# Shett_3.net
KiCad netlist of a schematic drawn in Altium Designer
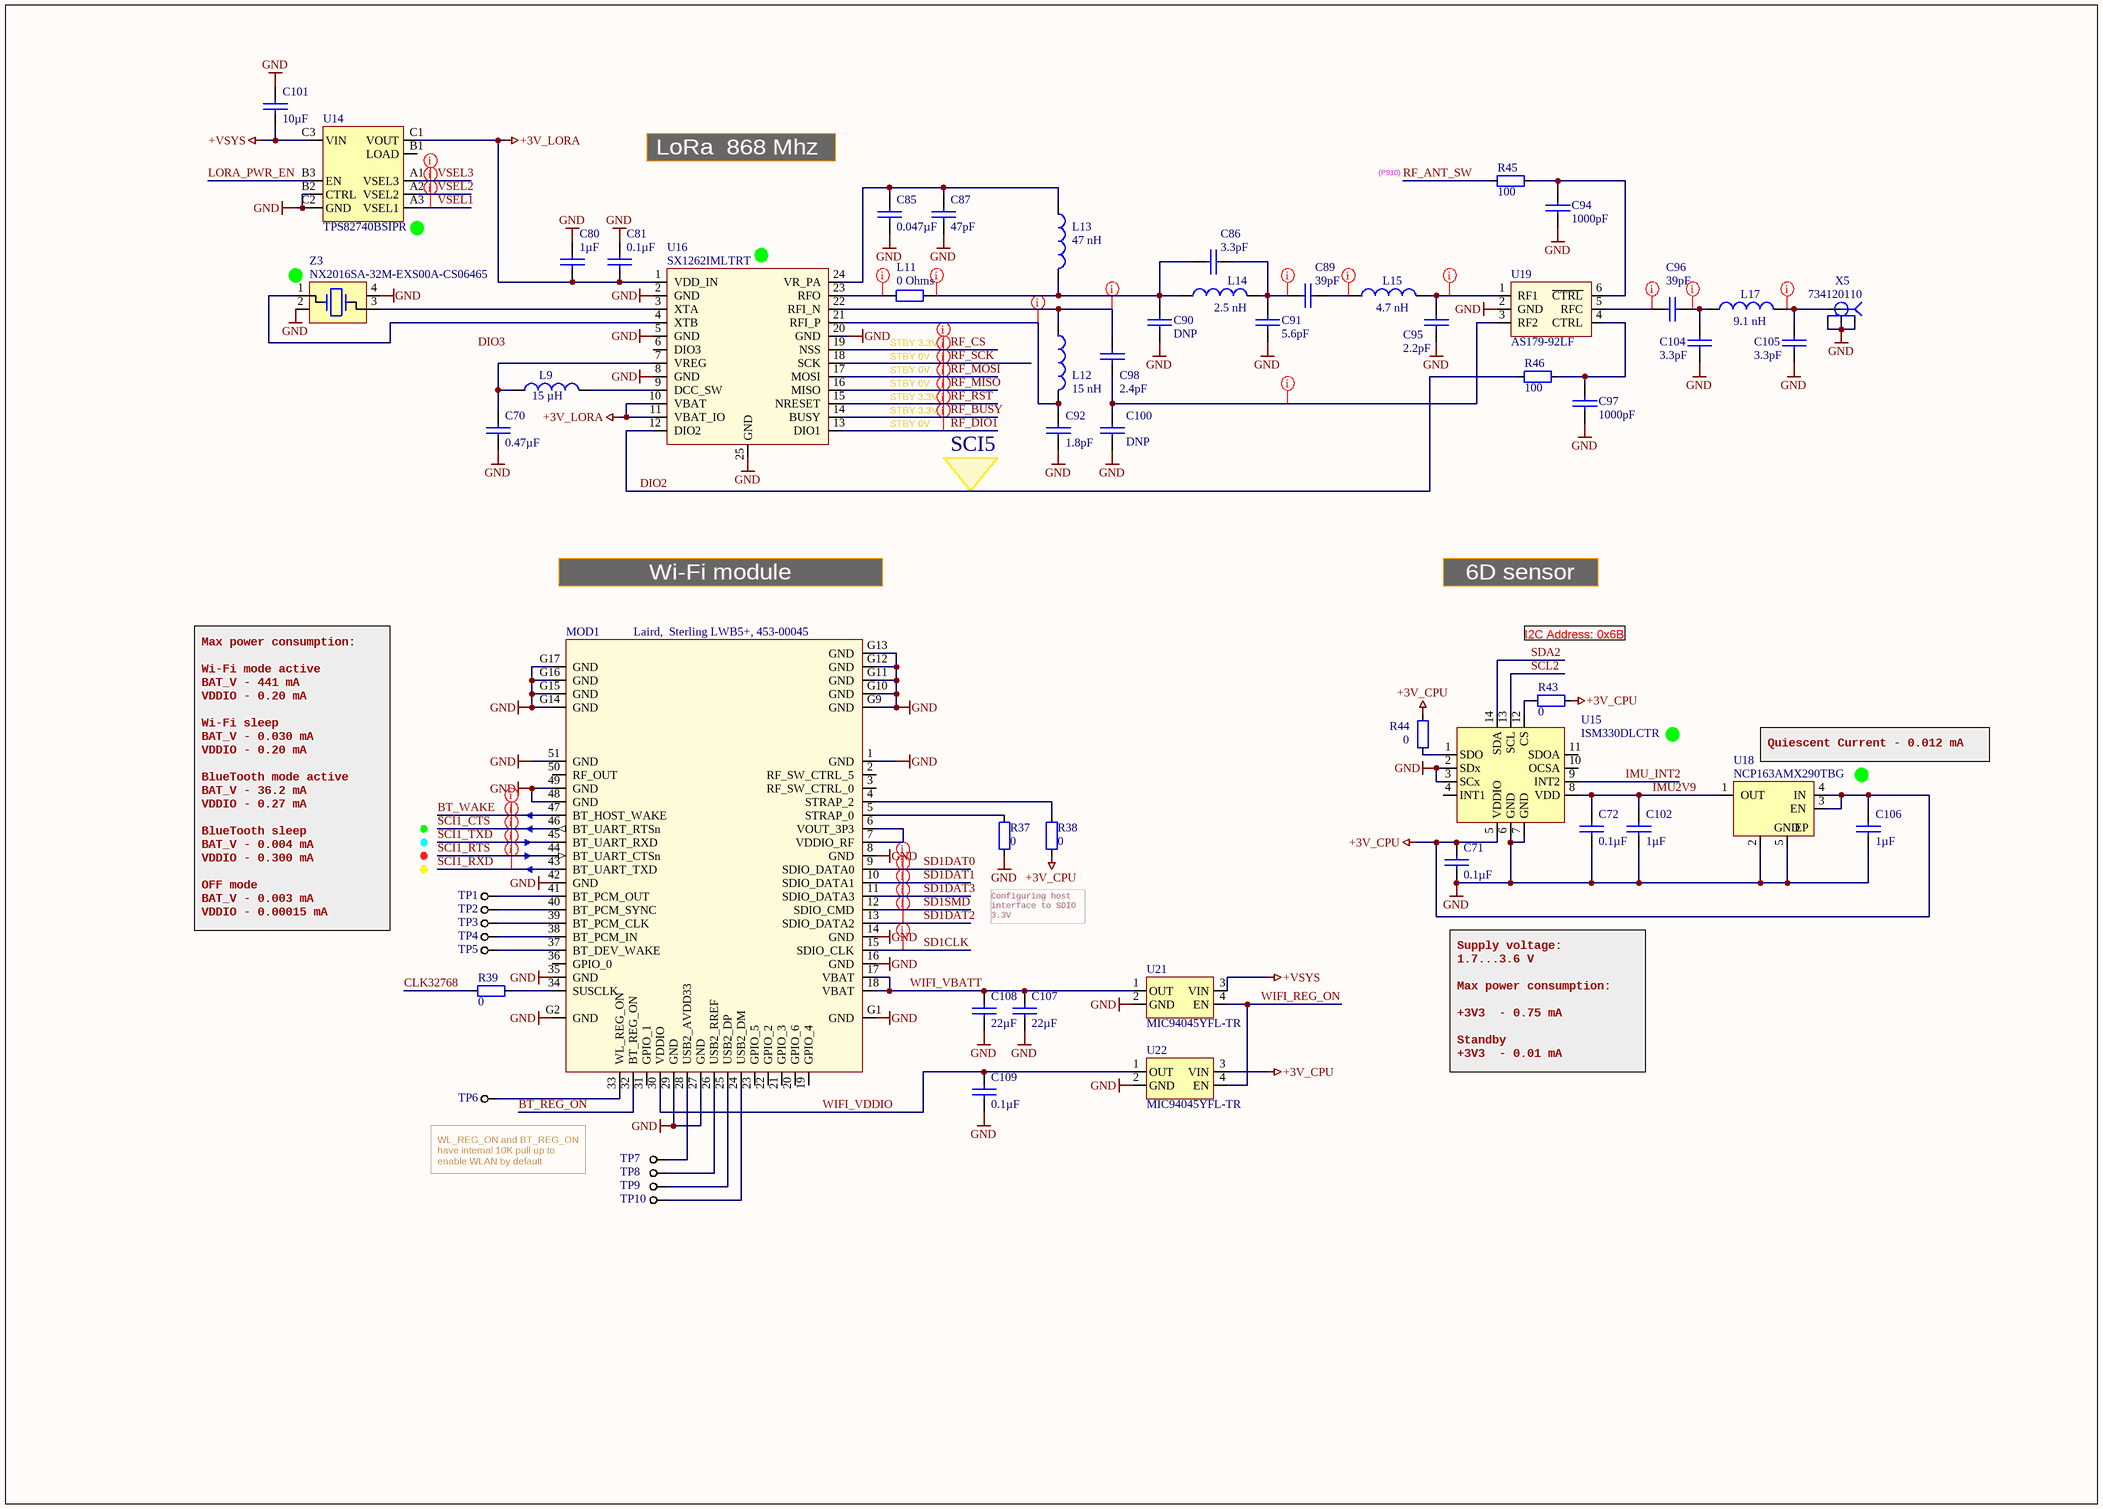
[diagram p0: Shett_3.SchDoc]

(export (version "E")
  (design (tool "Eeschema 10.0.6"))
  (components
    (comp (ref "C70")
      (value "0.47µF")
      (footprint "0402 CAP")
      (description "0.47µF, ±20%, 25V, X5R, 0402 (1005 Metric), -55°C ~ 85°C, -, Automotive")
      (fields
        (field (name "PART NUMBER") "GRT155R61E474ME01D")
        (field (name "MANUFACTURER") "Murata Electronics North America")
      )
      (libsource (lib "ea_PassivComps") (part "Capacitor"))
    )
    (comp (ref "C71")
      (value "0.1µF")
      (footprint "0402 CAP")
      (description "0.1µF, ±10%, 50V, X7R, 0402 (1005 Metric), -55°C ~ 125°C, -, General Purpose")
      (fields
        (field (name "PART NUMBER") "0402B104K500CT")
        (field (name "MANUFACTURER") "Walsin Technology Corporation")
      )
      (libsource (lib "ea_PassivComps") (part "Capacitor"))
    )
    (comp (ref "C72")
      (value "0.1µF")
      (footprint "0402 CAP")
      (description "0.1µF, ±10%, 50V, X7R, 0402 (1005 Metric), -55°C ~ 125°C, -, General Purpose")
      (fields
        (field (name "PART NUMBER") "0402B104K500CT")
        (field (name "MANUFACTURER") "Walsin Technology Corporation")
      )
      (libsource (lib "ea_PassivComps") (part "Capacitor"))
    )
    (comp (ref "C80")
      (value "1µF")
      (footprint "0402 CAP")
      (description "1µF, ±20%, 25V, X5R, 0402 (1005 Metric), -55°C ~ 85°C, -, General Purpose")
      (fields (field (name "PART NUMBER") "TMK105BJ105MV-F") (field (name "MANUFACTURER") "Taiyo Yuden"))
      (libsource (lib "ea_PassivComps") (part "Capacitor"))
    )
    (comp (ref "C81")
      (value "0.1µF")
      (footprint "0402 CAP")
      (description "0.1µF, ±10%, 50V, X7R, 0402 (1005 Metric), -55°C ~ 125°C, -, General Purpose")
      (fields
        (field (name "PART NUMBER") "0402B104K500CT")
        (field (name "MANUFACTURER") "Walsin Technology Corporation")
      )
      (libsource (lib "ea_PassivComps") (part "Capacitor"))
    )
    (comp (ref "C85")
      (value "0.047µF")
      (footprint "0402 CAP")
      (description "0.047µF, ±10%, 25V, X7R, 0402 (1005 Metric), -55°C ~ 125°C, -, General Purpose")
      (fields (field (name "PART NUMBER") "CC0402KRX7R8BB473") (field (name "MANUFACTURER") "Yageo"))
      (libsource (lib "ea_PassivComps") (part "Capacitor"))
    )
    (comp (ref "C86")
      (value "3.3pF")
      (footprint "0402 CAP")
      (description "3.3pF, ±0.1pF, 50V, C0G, NP0, 0402 (1005 Metric), -55°C ~ 125°C, -, RF, Microwave, High Frequency")
      (fields
        (field (name "PART NUMBER") "885392005011")
        (field (name "MANUFACTURER") "Wurth Electronics Inc.")
      )
      (libsource (lib "ea_PassivComps") (part "Capacitor"))
    )
    (comp (ref "C87")
      (value "47pF")
      (footprint "0402 CAP")
      (fields
        (field (name "PART NUMBER") "GJM1555C1H470FB01D")
        (field (name "MANUFACTURER") "Murata Electronics North America")
        (field (name "PARTNUM") "490-16376-1-ND")
      )
      (libsource (lib "ea_PassivComps") (part "Capacitor"))
    )
    (comp (ref "C89")
      (value "39pF")
      (footprint "0402 CAP")
      (fields
        (field (name "PART NUMBER") "GJM1555C1H390JB01D")
        (field (name "MANUFACTURER") "Murata Electronics North America")
        (field (name "PARTNUM") "490-17673-1-ND")
      )
      (libsource (lib "ea_PassivComps") (part "Capacitor"))
    )
    (comp (ref "C90")
      (value "DNP")
      (footprint "0402 CAP")
      (fields (field (name "Comment") "Capacitor_0402"))
      (libsource (lib "ea_Capacitors") (part "Capacitor_0402"))
    )
    (comp (ref "C91")
      (value "5.6pF")
      (footprint "0402 CAP")
      (fields
        (field (name "PART NUMBER") "GJM1555C1H5R6BB01D")
        (field (name "MANUFACTURER") "Murata Electronics North America")
        (field (name "PARTNUM") "490-11225-1-ND")
      )
      (libsource (lib "ea_PassivComps") (part "Capacitor"))
    )
    (comp (ref "C92")
      (value "1.8pF")
      (footprint "0402 CAP")
      (fields
        (field (name "PART NUMBER") "GJM1555C1H1R8BB01D")
        (field (name "MANUFACTURER") "Murata Electronics North America")
        (field (name "PARTNUM") "490-8089-1-ND")
      )
      (libsource (lib "ea_PassivComps") (part "Capacitor"))
    )
    (comp (ref "C94")
      (value "1000pF")
      (footprint "0402 CAP")
      (description "1000pF, ±5%, 50V, CH, 0402 (1005 Metric), -25°C ~ 85°C, Low ESL, General Purpose")
      (fields
        (field (name "PART NUMBER") "C1005CH1H102J050BA")
        (field (name "MANUFACTURER") "TDK Corporation")
      )
      (libsource (lib "ea_PassivComps") (part "Capacitor"))
    )
    (comp (ref "C95")
      (value "2.2pF")
      (footprint "0402 CAP")
      (fields
        (field (name "PART NUMBER") "CBR04C229B5GAC")
        (field (name "MANUFACTURER") "KEMET")
        (field (name "PARTNUM") "399-17527-1-ND")
      )
      (libsource (lib "ea_PassivComps") (part "Capacitor"))
    )
    (comp (ref "C96")
      (value "39pF")
      (footprint "0402 CAP")
      (fields
        (field (name "PART NUMBER") "GJM1555C1H390JB01D")
        (field (name "MANUFACTURER") "Murata Electronics North America")
        (field (name "PARTNUM") "490-17673-1-ND")
      )
      (libsource (lib "ea_PassivComps") (part "Capacitor"))
    )
    (comp (ref "C97")
      (value "1000pF")
      (footprint "0402 CAP")
      (description "1000pF, ±5%, 50V, CH, 0402 (1005 Metric), -25°C ~ 85°C, Low ESL, General Purpose")
      (fields
        (field (name "PART NUMBER") "C1005CH1H102J050BA")
        (field (name "MANUFACTURER") "TDK Corporation")
      )
      (libsource (lib "ea_PassivComps") (part "Capacitor"))
    )
    (comp (ref "C98")
      (value "2.4pF")
      (footprint "0402 CAP")
      (fields
        (field (name "PART NUMBER") "GJM1555C1H2R4BB01D")
        (field (name "MANUFACTURER") "Murata Electronics North America")
        (field (name "PARTNUM") "490-8093-1-ND")
      )
      (libsource (lib "ea_PassivComps") (part "Capacitor"))
    )
    (comp (ref "C100")
      (value "DNP")
      (footprint "0402 CAP")
      (fields (field (name "Comment") "Capacitor_0402"))
      (libsource (lib "ea_Capacitors") (part "Capacitor_0402"))
    )
    (comp (ref "C101")
      (value "10µF")
      (footprint "0603 CAP")
      (description "10µF, ±10%, 16V, X5R, 0603 (1608 Metric), -55°C ~ 85°C, -, Automotive")
      (fields
        (field (name "PART NUMBER") "GRT188R61C106KE13D")
        (field (name "MANUFACTURER") "Murata Electronics North America")
      )
      (libsource (lib "ea_PassivComps") (part "Capacitor"))
    )
    (comp (ref "C102")
      (value "1µF")
      (footprint "0402 CAP")
      (description "1µF, ±20%, 25V, X5R, 0402 (1005 Metric), -55°C ~ 85°C, -, General Purpose")
      (fields (field (name "PART NUMBER") "TMK105BJ105MV-F") (field (name "MANUFACTURER") "Taiyo Yuden"))
      (libsource (lib "ea_PassivComps") (part "Capacitor"))
    )
    (comp (ref "C104")
      (value "3.3pF")
      (footprint "0402 CAP")
      (description "3.3pF, ±0.1pF, 50V, C0G, NP0, 0402 (1005 Metric), -55°C ~ 125°C, -, RF, Microwave, High Frequency")
      (fields
        (field (name "PART NUMBER") "885392005011")
        (field (name "MANUFACTURER") "Wurth Electronics Inc.")
      )
      (libsource (lib "ea_PassivComps") (part "Capacitor"))
    )
    (comp (ref "C105")
      (value "3.3pF")
      (footprint "0402 CAP")
      (description "3.3pF, ±0.1pF, 50V, C0G, NP0, 0402 (1005 Metric), -55°C ~ 125°C, -, RF, Microwave, High Frequency")
      (fields
        (field (name "PART NUMBER") "885392005011")
        (field (name "MANUFACTURER") "Wurth Electronics Inc.")
      )
      (libsource (lib "ea_PassivComps") (part "Capacitor"))
    )
    (comp (ref "C106")
      (value "1µF")
      (footprint "0402 CAP")
      (description "1µF, ±20%, 25V, X5R, 0402 (1005 Metric), -55°C ~ 85°C, -, General Purpose")
      (fields (field (name "PART NUMBER") "TMK105BJ105MV-F") (field (name "MANUFACTURER") "Taiyo Yuden"))
      (libsource (lib "ea_PassivComps") (part "Capacitor"))
    )
    (comp (ref "C107")
      (value "22µF")
      (footprint "0603 CAP")
      (description "22µF, ±20%, 10V, X5R, 0603 (1608 Metric), -55°C ~ 85°C, -, SMPS Filtering")
      (fields (field (name "PART NUMBER") "LMK107BBJ226MA-T") (field (name "MANUFACTURER") "Taiyo Yuden"))
      (libsource (lib "ea_PassivComps") (part "Capacitor"))
    )
    (comp (ref "C108")
      (value "22µF")
      (footprint "0603 CAP")
      (description "22µF, ±20%, 10V, X5R, 0603 (1608 Metric), -55°C ~ 85°C, -, SMPS Filtering")
      (fields (field (name "PART NUMBER") "LMK107BBJ226MA-T") (field (name "MANUFACTURER") "Taiyo Yuden"))
      (libsource (lib "ea_PassivComps") (part "Capacitor"))
    )
    (comp (ref "C109")
      (value "0.1µF")
      (footprint "0402 CAP")
      (description "0.1µF, ±10%, 50V, X7R, 0402 (1005 Metric), -55°C ~ 125°C, -, General Purpose")
      (fields
        (field (name "PART NUMBER") "0402B104K500CT")
        (field (name "MANUFACTURER") "Walsin Technology Corporation")
      )
      (libsource (lib "ea_PassivComps") (part "Capacitor"))
    )
    (comp (ref "L9")
      (value "15 µH")
      (footprint "2012[0805]")
      (description "15 µH Shielded Multilayer Inductor 250 mA, 1.235Ohm, 24MHz Max 0805 (2012 Metric)")
      (fields
        (field (name "MANUFACTURER") "Murata Electronics")
        (field (name "PARTNUM") "490-LQM21DH150M70LCT-ND")
      )
      (libsource (lib "ea_RF_inductors") (part "LQM21DH150M70L"))
    )
    (comp (ref "L11")
      (value "0 Ohms")
      (footprint "INDC1005-0402")
      (description "0 Ohms Jumper 0.063W, 1/16W Chip Resistor 0402 (1005 Metric) Automotive AEC-Q200 Thick Film")
      (fields (field (name "MANUFACTURER") "Vishay Dale") (field (name "PARTNUM") "541-0.0JCT-ND"))
      (libsource (lib "ea_RF_inductors") (part "CRCW04020000Z0ED"))
    )
    (comp (ref "L12")
      (value "15 nH")
      (footprint "INDC1005-0402")
      (description "15nH Unshielded Wirewound Inductor 460mA 160 mOhm Max 0402 (1006 Metric)")
      (fields (field (name "MANUFACTURER") "Murata") (field (name "TOLERANCE") "±3%"))
      (libsource (lib "ea_RF_inductors") (part "LQW15AN15NH00D"))
    )
    (comp (ref "L13")
      (value "47 nH")
      (footprint "INDC1005-0402")
      (description "47nH Unshielded Wirewound Inductor 210mA 1.08 Ohm Max 0402 (1005 Metric)")
      (fields (field (name "MANUFACTURER") "Murata") (field (name "TOLERANCE") "±5%"))
      (libsource (lib "ea_RF_inductors") (part "LQW15AN47NJ00D"))
    )
    (comp (ref "L14")
      (value "2.5 nH")
      (footprint "INDC1005-0402")
      (description "2.5nH Unshielded Wirewound Inductor 850mA 50 mOhm Max 0402 (1006 Metric)")
      (fields (field (name "MANUFACTURER") "Murata") (field (name "TOLERANCE") "±0.2nH"))
      (libsource (lib "ea_RF_inductors") (part "LQW15AN2N5C00D"))
    )
    (comp (ref "L15")
      (value "4.7 nH")
      (footprint "INDC1005-0402")
      (description "4.7nH Unshielded Wirewound Inductor 750mA 70 mOhm Max 0402 (1006 Metric)")
      (fields
        (field (name "MANUFACTURER") "Murata Electronics North America")
        (field (name "TOLERANCE") "±0.2nH")
      )
      (libsource (lib "ea_RF_inductors") (part "LQW15AN4N7C00D"))
    )
    (comp (ref "L17")
      (value "9.1 nH")
      (footprint "INDC1005-0402")
      (description "9.1nH Unshielded Wirewound Inductor 540mA 140 mOhm Max 0402 (1006 Metric)")
      (fields
        (field (name "MANUFACTURER") "Murata Electronics North America")
        (field (name "TOLERANCE") "±3%")
      )
      (libsource (lib "ea_RF_inductors") (part "LQW15AN9N1H00D"))
    )
    (comp (ref "MOD1")
      (value "Laird,  Sterling LWB5+, 453-00045")
      (footprint "LWB5+ 453-00045C ver S7V30")
      (description "Module, Sterling LWB5+")
      (fields (field (name "MANUFACTURER") "Laird"))
      (libsource (lib "ea_WiFi_modules") (part "CMP-MOD-453-00012-1.4_ver_S7V30"))
    )
    (comp (ref "R37")
      (value "0")
      (footprint "0402")
      (description "0 Ohms Jumper 0.063W, 1/16W Chip Resistor 0402 (1005 Metric) Thick Film")
      (fields (field (name "MANUFACTURER") "Walsin Technology Corporation") (field (name "VOLTAGE") "50 V"))
      (libsource (lib "") (part "WR04X000 PTL_1"))
    )
    (comp (ref "R38")
      (value "0")
      (footprint "0402")
      (description "0 Ohms Jumper 0.063W, 1/16W Chip Resistor 0402 (1005 Metric) Thick Film")
      (fields (field (name "MANUFACTURER") "Walsin Technology Corporation") (field (name "VOLTAGE") "50 V"))
      (libsource (lib "") (part "WR04X000 PTL_1"))
    )
    (comp (ref "R39")
      (value "0")
      (footprint "0402")
      (description "0 Ohms Jumper 0.063W, 1/16W Chip Resistor 0402 (1005 Metric) Thick Film")
      (fields (field (name "MANUFACTURER") "Walsin Technology Corporation") (field (name "VOLTAGE") "50 V"))
      (libsource (lib "ea_Resistors_0402") (part "WR04X000 PTL"))
    )
    (comp (ref "R43")
      (value "0")
      (footprint "0402")
      (description "0 Ohms Jumper 0.063W, 1/16W Chip Resistor 0402 (1005 Metric) Thick Film")
      (fields (field (name "MANUFACTURER") "Walsin Technology Corporation") (field (name "VOLTAGE") "50 V"))
      (libsource (lib "ea_Resistors_0402") (part "WR04X000 PTL"))
    )
    (comp (ref "R44")
      (value "0")
      (footprint "0402")
      (description "0 Ohms Jumper 0.063W, 1/16W Chip Resistor 0402 (1005 Metric) Thick Film")
      (fields (field (name "MANUFACTURER") "Walsin Technology Corporation") (field (name "VOLTAGE") "50 V"))
      (libsource (lib "") (part "WR04X000 PTL_1"))
    )
    (comp (ref "R45")
      (value "100")
      (footprint "0402")
      (fields
        (field (name "MANUFACTURER") "Stackpole Electronics Inc")
        (field (name "TOLERANCE") "±1%")
        (field (name "VOLTAGE") "75V")
      )
      (libsource (lib "ea_PassivComps") (part "Resistor"))
    )
    (comp (ref "R46")
      (value "100")
      (footprint "0402")
      (fields
        (field (name "MANUFACTURER") "Stackpole Electronics Inc")
        (field (name "TOLERANCE") "±1%")
        (field (name "VOLTAGE") "75V")
      )
      (libsource (lib "ea_PassivComps") (part "Resistor"))
    )
    (comp (ref "TP1")
      (value "Test_point 0.5 мм")
      (footprint "Test point 0.5 мм")
      (libsource (lib "ea_Contacts") (part "Test_point 0.5 мм"))
    )
    (comp (ref "TP2")
      (value "Test_point 0.5 мм")
      (footprint "Test point 0.5 мм")
      (libsource (lib "ea_Contacts") (part "Test_point 0.5 мм"))
    )
    (comp (ref "TP3")
      (value "Test_point 0.5 мм")
      (footprint "Test point 0.5 мм")
      (libsource (lib "ea_Contacts") (part "Test_point 0.5 мм"))
    )
    (comp (ref "TP4")
      (value "Test_point 0.5 мм")
      (footprint "Test point 0.5 мм")
      (libsource (lib "ea_Contacts") (part "Test_point 0.5 мм"))
    )
    (comp (ref "TP5")
      (value "Test_point 0.5 мм")
      (footprint "Test point 0.5 мм")
      (libsource (lib "ea_Contacts") (part "Test_point 0.5 мм"))
    )
    (comp (ref "TP6")
      (value "Test_point 0.5 мм")
      (footprint "Test point 0.5 мм")
      (libsource (lib "ea_Contacts") (part "Test_point 0.5 мм"))
    )
    (comp (ref "TP7")
      (value "Test_point 0.5 мм")
      (footprint "Test point 0.5 мм")
      (libsource (lib "ea_Contacts") (part "Test_point 0.5 мм"))
    )
    (comp (ref "TP8")
      (value "Test_point 0.5 мм")
      (footprint "Test point 0.5 мм")
      (libsource (lib "ea_Contacts") (part "Test_point 0.5 мм"))
    )
    (comp (ref "TP9")
      (value "Test_point 0.5 мм")
      (footprint "Test point 0.5 мм")
      (libsource (lib "ea_Contacts") (part "Test_point 0.5 мм"))
    )
    (comp (ref "TP10")
      (value "Test_point 0.5 мм")
      (footprint "Test point 0.5 мм")
      (libsource (lib "ea_Contacts") (part "Test_point 0.5 мм"))
    )
    (comp (ref "U14")
      (value "TPS82740BSIPR")
      (footprint "MicroSiP")
      (fields (field (name "MANUFACTURER") "Texas Instruments") (field (name "PARTNUM") "296-46481-1-ND"))
      (libsource (lib "ea_IC_Power_Reg_Ref_Sw") (part "TPS82740BSIPR"))
    )
    (comp (ref "U15")
      (value "ISM330DLCTR")
      (footprint "LGA-14 BOSCH")
      (description "Accelerometer, Gyroscope, Temperature, 3 Axis Sensor I²C, SPI , -40°C ~ 85°C, 14-LGA (2.5x3)")
      (fields (field (name "MANUFACTURER") "STMicroelectronics") (field (name "PARTNUM") "497-17583-1-ND"))
      (libsource (lib "ea_IC_sensors") (part "ISM330DLCTR"))
    )
    (comp (ref "U16")
      (value "SX1262IMLTRT")
      (footprint "VQFN24")
      (description "IC RF TxRx Only General ISM < 1GHz LoRaWAN 150MHz ~ 960MHz 24-VFQFN Exposed Pad")
      (fields (field (name "MANUFACTURER") "Semtech Corporation"))
      (libsource (lib "ea_IC_RF") (part "SX1262IMLTRT"))
    )
    (comp (ref "U18")
      (value "NCP163AMX290TBG")
      (footprint "4-XDFN")
      (description "LDO 2.9V, 250 mA, Vin < 5.5V, Iq < 20uA, PSSR 91dB ~ 60dB, -40..+125 C,  4-XDFN (1x1)")
      (fields
        (field (name "MANUFACTURER") "ON Semiconductor")
        (field (name "PARTNUM") "NCP163AMX290TBGOSCT-ND")
      )
      (libsource (lib "ea_IC_Linear_reg_LDO") (part "NCP163AMX290TBG"))
    )
    (comp (ref "U19")
      (value "AS179-92LF")
      (footprint "SC70-6")
      (description "RF Switch IC 802.11b, g, Bluetooth, WLAN SPDT 3 GHz 50Ohm SC-70-6, -40°C ~ 85°C")
      (fields
        (field (name "MANUFACTURER") "Skyworks Solutions Inc.")
        (field (name "PARTNUM") "863-1003-1-ND")
        (field (name "PARTNAME") "AS179-92LF")
      )
      (libsource (lib "ea_IC_RF") (part "AS179-92LF"))
    )
    (comp (ref "U21")
      (value "MIC94045YFL-TR")
      (footprint "4-WDFN")
      (description "Power Switch P-Channel, 1.7V ~ 5.5V, 3A, 28 mOhm,   4-MLF® (1.2x1.2), -40...125 C")
      (fields (field (name "MANUFACTURER") "Microchip Technology") (field (name "PARTNUM") "576-3973-1-ND"))
      (libsource (lib "MIC94045") (part "MIC94045YFL-TR"))
    )
    (comp (ref "U22")
      (value "MIC94045YFL-TR")
      (footprint "4-WDFN")
      (description "Power Switch P-Channel, 1.7V ~ 5.5V, 3A, 28 mOhm,   4-MLF® (1.2x1.2), -40...125 C")
      (fields (field (name "MANUFACTURER") "Microchip Technology") (field (name "PARTNUM") "576-3973-1-ND"))
      (libsource (lib "MIC94045") (part "MIC94045YFL-TR"))
    )
    (comp (ref "X5")
      (value "734120110")
      (footprint "0734120110")
      (description "U.FL (UMCC) Connector Receptacle, Male Pin 50 Ohm Surface Mount Solder")
      (fields (field (name "MANUFACTURER") "Molex") (field (name "PARTNUM") "WM5587TR-ND"))
      (libsource (lib "ea_Connectors_RF") (part "0734120110"))
    )
    (comp (ref "Z3")
      (value "NX2016SA-32M-EXS00A-CS06465")
      (footprint "4-SMD 2.00mm x 1.60mm")
      (description "32 MHz Crystal 10pF,  60 Ohms, 10 ppm,  4-SMD, No Lead, -40...+85 С")
      (fields (field (name "MANUFACTURER") "NDK America, Inc.") (field (name "PARTNUM") "644-1300-1-ND"))
      (libsource (lib "ea_OSC_CLK_GEN") (part "NX2016SA-32M-EXS00A-CS06465"))
    )
  )
  (nets
    (net (code "1") (name "+3V_CPU") (class "Default")
      (node (ref "C106") (pin "1") (pinfunction "1_1") (pintype "passive"))
      (node (ref "C71") (pin "1") (pinfunction "1_1") (pintype "passive"))
      (node (ref "R38") (pin "1") (pinfunction "1_1") (pintype "passive"))
      (node (ref "R43") (pin "1") (pinfunction "1_1") (pintype "passive"))
      (node (ref "R44") (pin "2") (pinfunction "2_2") (pintype "passive"))
      (node (ref "U15") (pin "5") (pinfunction "VDDIO_5") (pintype "passive"))
      (node (ref "U18") (pin "3") (pinfunction "EN_3") (pintype "power_in"))
      (node (ref "U18") (pin "4") (pinfunction "IN_4") (pintype "power_in"))
      (node (ref "U22") (pin "3") (pinfunction "VIN_3") (pintype "passive"))
    )
    (net (code "2") (name "+3V_LORA") (class "Default")
      (node (ref "C80") (pin "2") (pinfunction "2_2") (pintype "passive"))
      (node (ref "C81") (pin "2") (pinfunction "2_2") (pintype "passive"))
      (node (ref "U14") (pin "C1") (pinfunction "VOUT_C1") (pintype "passive"))
      (node (ref "U16") (pin "1") (pinfunction "VDD_IN_1") (pintype "power_in"))
      (node (ref "U16") (pin "10") (pinfunction "VBAT_10") (pintype "power_in"))
      (node (ref "U16") (pin "11") (pinfunction "VBAT_IO_11") (pintype "power_in"))
    )
    (net (code "3") (name "+VSYS") (class "Default")
      (node (ref "C101") (pin "2") (pinfunction "2_2") (pintype "passive"))
      (node (ref "U14") (pin "C3") (pinfunction "VIN_C3") (pintype "passive"))
      (node (ref "U21") (pin "3") (pinfunction "VIN_3") (pintype "passive"))
    )
    (net (code "4") (name "/BT_REG_ON") (class "Default")
      (node (ref "MOD1") (pin "32") (pinfunction "BT_REG_ON_32") (pintype "passive"))
    )
    (net (code "5") (name "/BT_WAKE") (class "Default")
      (node (ref "MOD1") (pin "47") (pinfunction "BT_HOST_WAKE_47") (pintype "passive"))
    )
    (net (code "6") (name "/CLK32768") (class "Default")
      (node (ref "R39") (pin "2") (pinfunction "2_2") (pintype "passive"))
    )
    (net (code "7") (name "/DIO2") (class "Default")
      (node (ref "R46") (pin "2") (pinfunction "2_2") (pintype "passive"))
      (node (ref "U16") (pin "12") (pinfunction "DIO2_12") (pintype "passive"))
    )
    (net (code "9") (name "/IMU2V9") (class "Default")
      (node (ref "C102") (pin "1") (pinfunction "1_1") (pintype "passive"))
      (node (ref "C72") (pin "1") (pinfunction "1_1") (pintype "passive"))
      (node (ref "U15") (pin "8") (pinfunction "VDD_8") (pintype "passive"))
      (node (ref "U18") (pin "1") (pinfunction "OUT_1") (pintype "power_in"))
    )
    (net (code "10") (name "/IMU_INT2") (class "Default")
      (node (ref "U15") (pin "9") (pinfunction "INT2_9") (pintype "passive"))
    )
    (net (code "11") (name "/LORA_PWR_EN") (class "Default")
      (node (ref "U14") (pin "B3") (pinfunction "EN_B3") (pintype "passive"))
    )
    (net (code "12") (name "/RF_ANT_SW") (class "Default")
      (node (ref "R45") (pin "2") (pinfunction "2_2") (pintype "passive"))
    )
    (net (code "13") (name "/RF_BUSY") (class "Default")
      (node (ref "U16") (pin "14") (pinfunction "BUSY_14") (pintype "passive"))
    )
    (net (code "14") (name "/RF_CS") (class "Default")
      (node (ref "U16") (pin "19") (pinfunction "NSS_19") (pintype "passive"))
    )
    (net (code "15") (name "/RF_DIO1") (class "Default")
      (node (ref "U16") (pin "13") (pinfunction "DIO1_13") (pintype "passive"))
    )
    (net (code "16") (name "/RF_MISO") (class "Default")
      (node (ref "U16") (pin "16") (pinfunction "MISO_16") (pintype "passive"))
    )
    (net (code "17") (name "/RF_MOSI") (class "Default")
      (node (ref "U16") (pin "17") (pinfunction "MOSI_17") (pintype "passive"))
    )
    (net (code "18") (name "/RF_RST") (class "Default")
      (node (ref "U16") (pin "15") (pinfunction "NRESET_15") (pintype "passive"))
    )
    (net (code "19") (name "/RF_SCK") (class "Default")
      (node (ref "U16") (pin "18") (pinfunction "SCK_18") (pintype "passive"))
    )
    (net (code "20") (name "/SCI1_CTS") (class "Default")
      (node (ref "MOD1") (pin "46") (pinfunction "BT_UART_RTSn_46") (pintype "output"))
    )
    (net (code "21") (name "/SCI1_RTS") (class "Default")
      (node (ref "MOD1") (pin "44") (pinfunction "BT_UART_CTSn_44") (pintype "input"))
    )
    (net (code "22") (name "/SCI1_RXD") (class "Default")
      (node (ref "MOD1") (pin "43") (pinfunction "BT_UART_TXD_43") (pintype "passive"))
    )
    (net (code "23") (name "/SCI1_TXD") (class "Default")
      (node (ref "MOD1") (pin "45") (pinfunction "BT_UART_RXD_45") (pintype "passive"))
    )
    (net (code "24") (name "/SCL2") (class "Default")
      (node (ref "U15") (pin "13") (pinfunction "SCL_13") (pintype "passive"))
    )
    (net (code "25") (name "/SD1CLK") (class "Default")
      (node (ref "MOD1") (pin "15") (pinfunction "SDIO_CLK_15") (pintype "passive"))
    )
    (net (code "26") (name "/SD1DAT0") (class "Default")
      (node (ref "MOD1") (pin "9") (pinfunction "SDIO_DATA0_9") (pintype "passive"))
    )
    (net (code "27") (name "/SD1DAT1") (class "Default")
      (node (ref "MOD1") (pin "10") (pinfunction "SDIO_DATA1_10") (pintype "passive"))
    )
    (net (code "28") (name "/SD1DAT2") (class "Default")
      (node (ref "MOD1") (pin "13") (pinfunction "SDIO_DATA2_13") (pintype "passive"))
    )
    (net (code "29") (name "/SD1DAT3") (class "Default")
      (node (ref "MOD1") (pin "11") (pinfunction "SDIO_DATA3_11") (pintype "passive"))
    )
    (net (code "30") (name "/SD1SMD") (class "Default")
      (node (ref "MOD1") (pin "12") (pinfunction "SDIO_CMD_12") (pintype "passive"))
    )
    (net (code "31") (name "/SDA2") (class "Default")
      (node (ref "U15") (pin "14") (pinfunction "SDA_14") (pintype "passive"))
    )
    (net (code "32") (name "/VSEL1") (class "Default")
      (node (ref "U14") (pin "A3") (pinfunction "VSEL1_A3") (pintype "passive"))
    )
    (net (code "33") (name "/VSEL2") (class "Default")
      (node (ref "U14") (pin "A2") (pinfunction "VSEL2_A2") (pintype "passive"))
    )
    (net (code "34") (name "/VSEL3") (class "Default")
      (node (ref "U14") (pin "A1") (pinfunction "VSEL3_A1") (pintype "passive"))
    )
    (net (code "35") (name "/WIFI_REG_ON") (class "Default")
      (node (ref "U21") (pin "4") (pinfunction "EN_4") (pintype "passive"))
      (node (ref "U22") (pin "4") (pinfunction "EN_4") (pintype "passive"))
    )
    (net (code "36") (name "/WIFI_VBATT") (class "Default")
      (node (ref "C107") (pin "1") (pinfunction "1_1") (pintype "passive"))
      (node (ref "C108") (pin "1") (pinfunction "1_1") (pintype "passive"))
      (node (ref "MOD1") (pin "17") (pinfunction "VBAT_17") (pintype "passive"))
      (node (ref "MOD1") (pin "18") (pinfunction "VBAT_18") (pintype "passive"))
      (node (ref "U21") (pin "1") (pinfunction "OUT_1") (pintype "passive"))
    )
    (net (code "37") (name "/WIFI_VDDIO") (class "Default")
      (node (ref "C109") (pin "1") (pinfunction "1_1") (pintype "passive"))
      (node (ref "MOD1") (pin "30") (pinfunction "VDDIO_30") (pintype "passive"))
      (node (ref "U22") (pin "1") (pinfunction "OUT_1") (pintype "passive"))
    )
    (net (code "38") (name "GND") (class "Default")
      (node (ref "C100") (pin "2") (pinfunction "2_2") (pintype "passive"))
      (node (ref "C101") (pin "1") (pinfunction "1_1") (pintype "passive"))
      (node (ref "C102") (pin "2") (pinfunction "2_2") (pintype "passive"))
      (node (ref "C104") (pin "1") (pinfunction "1_1") (pintype "passive"))
      (node (ref "C105") (pin "1") (pinfunction "1_1") (pintype "passive"))
      (node (ref "C106") (pin "2") (pinfunction "2_2") (pintype "passive"))
      (node (ref "C107") (pin "2") (pinfunction "2_2") (pintype "passive"))
      (node (ref "C108") (pin "2") (pinfunction "2_2") (pintype "passive"))
      (node (ref "C109") (pin "2") (pinfunction "2_2") (pintype "passive"))
      (node (ref "C70") (pin "2") (pinfunction "2_2") (pintype "passive"))
      (node (ref "C71") (pin "2") (pinfunction "2_2") (pintype "passive"))
      (node (ref "C72") (pin "2") (pinfunction "2_2") (pintype "passive"))
      (node (ref "C80") (pin "1") (pinfunction "1_1") (pintype "passive"))
      (node (ref "C81") (pin "1") (pinfunction "1_1") (pintype "passive"))
      (node (ref "C85") (pin "2") (pinfunction "2_2") (pintype "passive"))
      (node (ref "C87") (pin "2") (pinfunction "2_2") (pintype "passive"))
      (node (ref "C90") (pin "2") (pinfunction "2_2") (pintype "passive"))
      (node (ref "C91") (pin "2") (pinfunction "2_2") (pintype "passive"))
      (node (ref "C92") (pin "2") (pinfunction "2_2") (pintype "passive"))
      (node (ref "C94") (pin "1") (pinfunction "1_1") (pintype "passive"))
      (node (ref "C95") (pin "2") (pinfunction "2_2") (pintype "passive"))
      (node (ref "C97") (pin "1") (pinfunction "1_1") (pintype "passive"))
      (node (ref "MOD1") (pin "1") (pinfunction "GND_1") (pintype "passive"))
      (node (ref "MOD1") (pin "14") (pinfunction "GND_14") (pintype "passive"))
      (node (ref "MOD1") (pin "16") (pinfunction "GND_16") (pintype "passive"))
      (node (ref "MOD1") (pin "27") (pinfunction "GND_27") (pintype "passive"))
      (node (ref "MOD1") (pin "29") (pinfunction "GND_29") (pintype "passive"))
      (node (ref "MOD1") (pin "35") (pinfunction "GND_35") (pintype "passive"))
      (node (ref "MOD1") (pin "42") (pinfunction "GND_42") (pintype "passive"))
      (node (ref "MOD1") (pin "48") (pinfunction "GND_48") (pintype "passive"))
      (node (ref "MOD1") (pin "49") (pinfunction "GND_49") (pintype "passive"))
      (node (ref "MOD1") (pin "51") (pinfunction "GND_51") (pintype "passive"))
      (node (ref "MOD1") (pin "8") (pinfunction "GND_8") (pintype "passive"))
      (node (ref "MOD1") (pin "G1") (pinfunction "GND_G1") (pintype "passive"))
      (node (ref "MOD1") (pin "G10") (pinfunction "GND_G10") (pintype "passive"))
      (node (ref "MOD1") (pin "G11") (pinfunction "GND_G11") (pintype "passive"))
      (node (ref "MOD1") (pin "G12") (pinfunction "GND_G12") (pintype "passive"))
      (node (ref "MOD1") (pin "G13") (pinfunction "GND_G13") (pintype "passive"))
      (node (ref "MOD1") (pin "G14") (pinfunction "GND_G14") (pintype "passive"))
      (node (ref "MOD1") (pin "G15") (pinfunction "GND_G15") (pintype "passive"))
      (node (ref "MOD1") (pin "G16") (pinfunction "GND_G16") (pintype "passive"))
      (node (ref "MOD1") (pin "G17") (pinfunction "GND_G17") (pintype "passive"))
      (node (ref "MOD1") (pin "G2") (pinfunction "GND_G2") (pintype "passive"))
      (node (ref "MOD1") (pin "G9") (pinfunction "GND_G9") (pintype "passive"))
      (node (ref "R37") (pin "1") (pinfunction "1_1") (pintype "passive"))
      (node (ref "U14") (pin "B2") (pinfunction "CTRL_B2") (pintype "passive"))
      (node (ref "U14") (pin "C2") (pinfunction "GND_C2") (pintype "passive"))
      (node (ref "U15") (pin "2") (pinfunction "SDx_2") (pintype "passive"))
      (node (ref "U15") (pin "3") (pinfunction "SCx_3") (pintype "passive"))
      (node (ref "U15") (pin "6") (pinfunction "GND_6") (pintype "passive"))
      (node (ref "U15") (pin "7") (pinfunction "GND_7") (pintype "passive"))
      (node (ref "U16") (pin "2") (pinfunction "GND_2") (pintype "passive"))
      (node (ref "U16") (pin "20") (pinfunction "GND_20") (pintype "passive"))
      (node (ref "U16") (pin "25") (pinfunction "GND_25") (pintype "passive"))
      (node (ref "U16") (pin "5") (pinfunction "GND_5") (pintype "passive"))
      (node (ref "U16") (pin "8") (pinfunction "GND_8") (pintype "passive"))
      (node (ref "U18") (pin "2") (pinfunction "GND_2") (pintype "power_in"))
      (node (ref "U18") (pin "5") (pinfunction "EP_5") (pintype "power_in"))
      (node (ref "U19") (pin "2") (pinfunction "GND_2") (pintype "passive"))
      (node (ref "U21") (pin "2") (pinfunction "GND_2") (pintype "passive"))
      (node (ref "U22") (pin "2") (pinfunction "GND_2") (pintype "passive"))
      (node (ref "X5") (pin "2") (pinfunction "2_2") (pintype "passive"))
      (node (ref "X5") (pin "3") (pinfunction "3_3") (pintype "passive"))
      (node (ref "X5") (pin "4") (pinfunction "3_4") (pintype "passive"))
      (node (ref "Z3") (pin "2") (pinfunction "2_2") (pintype "passive"))
      (node (ref "Z3") (pin "4") (pinfunction "4_4") (pintype "passive"))
    )
    (net (code "39") (name "Net-(C86-Pad1)") (class "Default")
      (node (ref "C86") (pin "1") (pinfunction "1_1") (pintype "passive"))
      (node (ref "C90") (pin "1") (pinfunction "1_1") (pintype "passive"))
      (node (ref "L11") (pin "2") (pinfunction "2_2") (pintype "passive"))
      (node (ref "L13") (pin "2") (pinfunction "2_2") (pintype "passive"))
      (node (ref "L14") (pin "1") (pinfunction "1_1") (pintype "passive"))
    )
    (net (code "40") (name "Net-(C86-Pad2)") (class "Default")
      (node (ref "C86") (pin "2") (pinfunction "2_2") (pintype "passive"))
      (node (ref "C89") (pin "1") (pinfunction "1_1") (pintype "passive"))
      (node (ref "C91") (pin "1") (pinfunction "1_1") (pintype "passive"))
      (node (ref "L14") (pin "2") (pinfunction "2_2") (pintype "passive"))
    )
    (net (code "41") (name "Net-(C89-Pad2)") (class "Default")
      (node (ref "C89") (pin "2") (pinfunction "2_2") (pintype "passive"))
      (node (ref "L15") (pin "1") (pinfunction "1_1") (pintype "passive"))
    )
    (net (code "42") (name "Net-(C104-Pad2)") (class "Default")
      (node (ref "C104") (pin "2") (pinfunction "2_2") (pintype "passive"))
      (node (ref "C96") (pin "2") (pinfunction "2_2") (pintype "passive"))
      (node (ref "L17") (pin "1") (pinfunction "1_1") (pintype "passive"))
    )
    (net (code "43") (name "Net-(MOD1-BT_DEV_WAKE)") (class "Default")
      (node (ref "MOD1") (pin "37") (pinfunction "BT_DEV_WAKE_37") (pintype "passive"))
      (node (ref "TP5") (pin "1") (pinfunction "1_1") (pintype "passive"))
    )
    (net (code "44") (name "Net-(MOD1-BT_PCM_CLK)") (class "Default")
      (node (ref "MOD1") (pin "39") (pinfunction "BT_PCM_CLK_39") (pintype "passive"))
      (node (ref "TP3") (pin "1") (pinfunction "1_1") (pintype "passive"))
    )
    (net (code "45") (name "Net-(MOD1-BT_PCM_IN)") (class "Default")
      (node (ref "MOD1") (pin "38") (pinfunction "BT_PCM_IN_38") (pintype "passive"))
      (node (ref "TP4") (pin "1") (pinfunction "1_1") (pintype "passive"))
    )
    (net (code "46") (name "Net-(MOD1-BT_PCM_OUT)") (class "Default")
      (node (ref "MOD1") (pin "41") (pinfunction "BT_PCM_OUT_41") (pintype "passive"))
      (node (ref "TP1") (pin "1") (pinfunction "1_1") (pintype "passive"))
    )
    (net (code "47") (name "Net-(MOD1-BT_PCM_SYNC)") (class "Default")
      (node (ref "MOD1") (pin "40") (pinfunction "BT_PCM_SYNC_40") (pintype "passive"))
      (node (ref "TP2") (pin "1") (pinfunction "1_1") (pintype "passive"))
    )
    (net (code "48") (name "Net-(MOD1-STRAP_0)") (class "Default")
      (node (ref "MOD1") (pin "5") (pinfunction "STRAP_0_5") (pintype "passive"))
      (node (ref "R37") (pin "2") (pinfunction "2_2") (pintype "passive"))
    )
    (net (code "49") (name "Net-(MOD1-STRAP_2)") (class "Default")
      (node (ref "MOD1") (pin "4") (pinfunction "STRAP_2_4") (pintype "passive"))
      (node (ref "R38") (pin "2") (pinfunction "2_2") (pintype "passive"))
    )
    (net (code "50") (name "Net-(MOD1-SUSCLK)") (class "Default")
      (node (ref "MOD1") (pin "34") (pinfunction "SUSCLK_34") (pintype "passive"))
      (node (ref "R39") (pin "1") (pinfunction "1_1") (pintype "passive"))
    )
    (net (code "51") (name "Net-(MOD1-USB2_AVDD33)") (class "Default")
      (node (ref "MOD1") (pin "28") (pinfunction "USB2_AVDD33_28") (pintype "passive"))
      (node (ref "TP7") (pin "1") (pinfunction "1_1") (pintype "passive"))
    )
    (net (code "52") (name "Net-(MOD1-USB2_DM)") (class "Default")
      (node (ref "MOD1") (pin "24") (pinfunction "USB2_DM_24") (pintype "passive"))
      (node (ref "TP10") (pin "1") (pinfunction "1_1") (pintype "passive"))
    )
    (net (code "53") (name "Net-(MOD1-USB2_DP)") (class "Default")
      (node (ref "MOD1") (pin "25") (pinfunction "USB2_DP_25") (pintype "passive"))
      (node (ref "TP9") (pin "1") (pinfunction "1_1") (pintype "passive"))
    )
    (net (code "54") (name "Net-(MOD1-USB2_RREF)") (class "Default")
      (node (ref "MOD1") (pin "26") (pinfunction "USB2_RREF_26") (pintype "passive"))
      (node (ref "TP8") (pin "1") (pinfunction "1_1") (pintype "passive"))
    )
    (net (code "55") (name "Net-(MOD1-VDDIO_RF)") (class "Default")
      (node (ref "MOD1") (pin "6") (pinfunction "VOUT_3P3_6") (pintype "passive"))
      (node (ref "MOD1") (pin "7") (pinfunction "VDDIO_RF_7") (pintype "passive"))
    )
    (net (code "56") (name "Net-(MOD1-WL_REG_ON)") (class "Default")
      (node (ref "MOD1") (pin "33") (pinfunction "WL_REG_ON_33") (pintype "passive"))
      (node (ref "TP6") (pin "1") (pinfunction "1_1") (pintype "passive"))
    )
    (net (code "57") (name "Net-(U15-CS)") (class "Default")
      (node (ref "R43") (pin "2") (pinfunction "2_2") (pintype "passive"))
      (node (ref "U15") (pin "12") (pinfunction "CS_12") (pintype "passive"))
    )
    (net (code "58") (name "Net-(U15-SDO)") (class "Default")
      (node (ref "R44") (pin "1") (pinfunction "1_1") (pintype "passive"))
      (node (ref "U15") (pin "1") (pinfunction "SDO_1") (pintype "passive"))
    )
    (net (code "59") (name "Net-(U16-DCC_SW)") (class "Default")
      (node (ref "L9") (pin "2") (pinfunction "2_2") (pintype "passive"))
      (node (ref "U16") (pin "9") (pinfunction "DCC_SW_9") (pintype "power_in"))
    )
    (net (code "60") (name "Net-(U16-RFI_N)") (class "Default")
      (node (ref "C98") (pin "1") (pinfunction "1_1") (pintype "passive"))
      (node (ref "L12") (pin "1") (pinfunction "1_1") (pintype "passive"))
      (node (ref "U16") (pin "22") (pinfunction "RFI_N_22") (pintype "passive"))
    )
    (net (code "61") (name "Net-(U16-RFI_P)") (class "Default")
      (node (ref "C92") (pin "1") (pinfunction "1_1") (pintype "passive"))
      (node (ref "L12") (pin "2") (pinfunction "2_2") (pintype "passive"))
      (node (ref "U16") (pin "21") (pinfunction "RFI_P_21") (pintype "passive"))
    )
    (net (code "62") (name "Net-(U16-RFO)") (class "Default")
      (node (ref "L11") (pin "1") (pinfunction "1_1") (pintype "passive"))
      (node (ref "U16") (pin "23") (pinfunction "RFO_23") (pintype "passive"))
    )
    (net (code "63") (name "Net-(U16-VREG)") (class "Default")
      (node (ref "C70") (pin "1") (pinfunction "1_1") (pintype "passive"))
      (node (ref "L9") (pin "1") (pinfunction "1_1") (pintype "passive"))
      (node (ref "U16") (pin "7") (pinfunction "VREG_7") (pintype "power_in"))
    )
    (net (code "64") (name "Net-(U16-VR_PA)") (class "Default")
      (node (ref "C85") (pin "1") (pinfunction "1_1") (pintype "passive"))
      (node (ref "C87") (pin "1") (pinfunction "1_1") (pintype "passive"))
      (node (ref "L13") (pin "1") (pinfunction "1_1") (pintype "passive"))
      (node (ref "U16") (pin "24") (pinfunction "VR_PA_24") (pintype "power_in"))
    )
    (net (code "65") (name "Net-(U16-XTA)") (class "Default")
      (node (ref "U16") (pin "3") (pinfunction "XTA_3") (pintype "passive"))
      (node (ref "Z3") (pin "3") (pintype "passive"))
    )
    (net (code "66") (name "Net-(U16-XTB)") (class "Default")
      (node (ref "U16") (pin "4") (pinfunction "XTB_4") (pintype "passive"))
      (node (ref "Z3") (pin "1") (pinfunction "1_1") (pintype "passive"))
    )
    (net (code "67") (name "Net-(U19-CTRL)") (class "Default")
      (node (ref "C97") (pin "2") (pinfunction "2_2") (pintype "passive"))
      (node (ref "R46") (pin "1") (pinfunction "1_1") (pintype "passive"))
      (node (ref "U19") (pin "4") (pinfunction "CTRL_4") (pintype "passive"))
    )
    (net (code "68") (name "Net-(U19-RF1)") (class "Default")
      (node (ref "C95") (pin "1") (pinfunction "1_1") (pintype "passive"))
      (node (ref "L15") (pin "2") (pinfunction "2_2") (pintype "passive"))
      (node (ref "U19") (pin "1") (pinfunction "RF1_1") (pintype "passive"))
    )
    (net (code "69") (name "Net-(U19-RF2)") (class "Default")
      (node (ref "C100") (pin "1") (pinfunction "1_1") (pintype "passive"))
      (node (ref "C98") (pin "2") (pinfunction "2_2") (pintype "passive"))
      (node (ref "U19") (pin "3") (pinfunction "RF2_3") (pintype "passive"))
    )
    (net (code "70") (name "Net-(U19-RFC)") (class "Default")
      (node (ref "C96") (pin "1") (pinfunction "1_1") (pintype "passive"))
      (node (ref "U19") (pin "5") (pinfunction "RFC_5") (pintype "passive"))
    )
    (net (code "71") (name "Net-(U19-~{CTRL})") (class "Default")
      (node (ref "C94") (pin "2") (pinfunction "2_2") (pintype "passive"))
      (node (ref "R45") (pin "1") (pinfunction "1_1") (pintype "passive"))
      (node (ref "U19") (pin "6") (pinfunction "~{CTRL}_6") (pintype "passive"))
    )
    (net (code "72") (name "Net-(X5-Sig)") (class "Default")
      (node (ref "C105") (pin "2") (pinfunction "2_2") (pintype "passive"))
      (node (ref "L17") (pin "2") (pinfunction "2_2") (pintype "passive"))
      (node (ref "X5") (pin "1") (pinfunction "Sig_1") (pintype "passive"))
    )
    (net (code "73") (name "unconnected-(MOD1-GPIO_0-Pad36)") (class "Default")
      (node (ref "MOD1") (pin "36") (pinfunction "GPIO_0_36") (pintype "passive"))
    )
    (net (code "74") (name "unconnected-(MOD1-GPIO_1-Pad31)") (class "Default")
      (node (ref "MOD1") (pin "31") (pinfunction "GPIO_1_31") (pintype "passive"))
    )
    (net (code "75") (name "unconnected-(MOD1-GPIO_2-Pad22)") (class "Default")
      (node (ref "MOD1") (pin "22") (pinfunction "GPIO_2_22") (pintype "passive"))
    )
    (net (code "76") (name "unconnected-(MOD1-GPIO_3-Pad21)") (class "Default")
      (node (ref "MOD1") (pin "21") (pinfunction "GPIO_3_21") (pintype "passive"))
    )
    (net (code "77") (name "unconnected-(MOD1-GPIO_4-Pad19)") (class "Default")
      (node (ref "MOD1") (pin "19") (pinfunction "GPIO_4_19") (pintype "passive"))
    )
    (net (code "78") (name "unconnected-(MOD1-GPIO_5-Pad23)") (class "Default")
      (node (ref "MOD1") (pin "23") (pinfunction "GPIO_5_23") (pintype "passive"))
    )
    (net (code "79") (name "unconnected-(MOD1-GPIO_6-Pad20)") (class "Default")
      (node (ref "MOD1") (pin "20") (pinfunction "GPIO_6_20") (pintype "passive"))
    )
    (net (code "80") (name "unconnected-(MOD1-RF_OUT-Pad50)") (class "Default")
      (node (ref "MOD1") (pin "50") (pinfunction "RF_OUT_50") (pintype "passive"))
    )
    (net (code "81") (name "unconnected-(MOD1-RF_SW_CTRL_0-Pad3)") (class "Default")
      (node (ref "MOD1") (pin "3") (pinfunction "RF_SW_CTRL_0_3") (pintype "passive"))
    )
    (net (code "82") (name "unconnected-(MOD1-RF_SW_CTRL_5-Pad2)") (class "Default")
      (node (ref "MOD1") (pin "2") (pinfunction "RF_SW_CTRL_5_2") (pintype "passive"))
    )
    (net (code "83") (name "unconnected-(U14-LOAD-PadB1)") (class "Default")
      (node (ref "U14") (pin "B1") (pinfunction "LOAD_B1") (pintype "passive"))
    )
    (net (code "84") (name "unconnected-(U15-INT1-Pad4)") (class "Default")
      (node (ref "U15") (pin "4") (pinfunction "INT1_4") (pintype "passive"))
    )
    (net (code "85") (name "unconnected-(U15-OCSA-Pad10)") (class "Default")
      (node (ref "U15") (pin "10") (pinfunction "OCSA_10") (pintype "passive"))
    )
    (net (code "86") (name "unconnected-(U15-SDOA-Pad11)") (class "Default")
      (node (ref "U15") (pin "11") (pinfunction "SDOA_11") (pintype "passive"))
    )
    (net (code "87") (name "unconnected-(U16-DIO3-Pad6)") (class "Default")
      (node (ref "U16") (pin "6") (pinfunction "DIO3_6") (pintype "passive"))
    )
  )
)
